# Grove_-_Alcohol_Sensor_v1_2.net
KiCad netlist of a schematic drawn in EAGLE
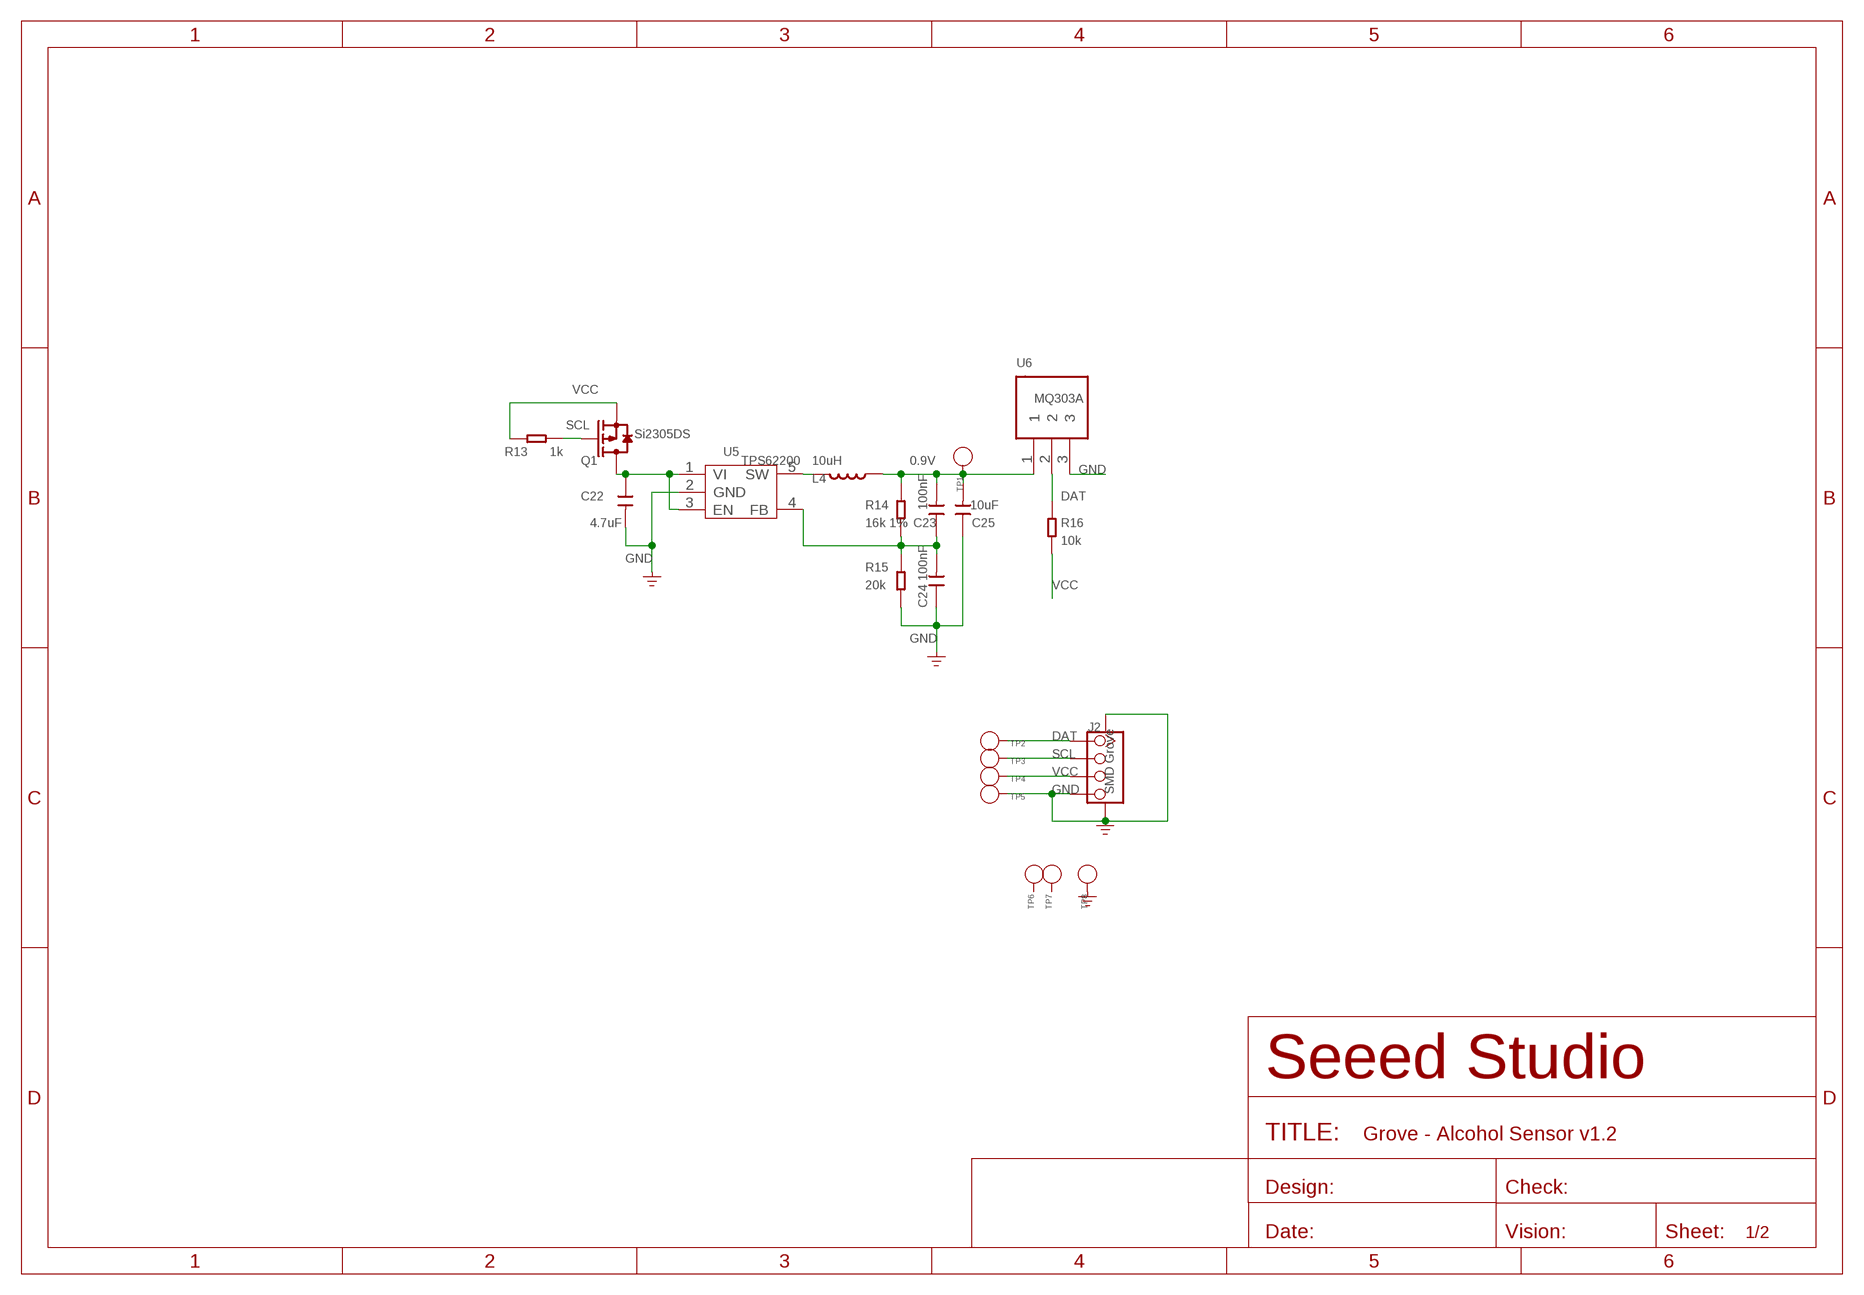
[diagram p0: schematic, sheet 1]
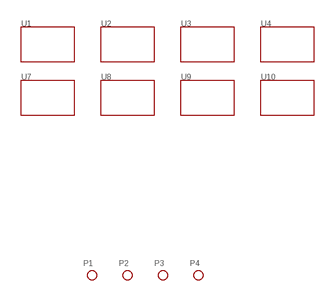
[diagram p1: schematic, sheet 2]

(export (version "E")
  (design (tool "Eeschema 10.0.6"))
  (components
    (comp (ref "P1")
      (value "PAD-MARK")
      (footprint "eagle-import:ROUND-MARK-1.0")
      (fields (field (name "PARTNO") "DNP"))
      (libsource (lib "eagle-import") (part "PAD-MARK"))
    )
    (comp (ref "P2")
      (value "PAD-MARK")
      (footprint "eagle-import:ROUND-MARK-1.0")
      (fields (field (name "PARTNO") "DNP"))
      (libsource (lib "eagle-import") (part "PAD-MARK"))
    )
    (comp (ref "P3")
      (value "PAD-MARK")
      (footprint "eagle-import:ROUND-MARK-1.0")
      (fields (field (name "PARTNO") "DNP"))
      (libsource (lib "eagle-import") (part "PAD-MARK"))
    )
    (comp (ref "P4")
      (value "PAD-MARK")
      (footprint "eagle-import:ROUND-MARK-1.0")
      (fields (field (name "PARTNO") "DNP"))
      (libsource (lib "eagle-import") (part "PAD-MARK"))
    )
    (comp (ref "U1")
      (value "TWIG'2U'")
      (footprint "eagle-import:GROVE-TEST-PLATFORM")
      (libsource (lib "eagle-import") (part "TWIG'2U'"))
    )
    (comp (ref "U2")
      (value "TWIG'2U'")
      (footprint "eagle-import:GROVE-TEST-PLATFORM")
      (libsource (lib "eagle-import") (part "TWIG'2U'"))
    )
    (comp (ref "U3")
      (value "TWIG'2U'")
      (footprint "eagle-import:GROVE-TEST-PLATFORM")
      (libsource (lib "eagle-import") (part "TWIG'2U'"))
    )
    (comp (ref "U4")
      (value "TWIG'2U'")
      (footprint "eagle-import:GROVE-TEST-PLATFORM")
      (libsource (lib "eagle-import") (part "TWIG'2U'"))
    )
    (comp (ref "U7")
      (value "TWIG'2U'")
      (footprint "eagle-import:GROVE-TEST-PLATFORM")
      (libsource (lib "eagle-import") (part "TWIG'2U'"))
    )
    (comp (ref "U8")
      (value "TWIG'2U'")
      (footprint "eagle-import:GROVE-TEST-PLATFORM")
      (libsource (lib "eagle-import") (part "TWIG'2U'"))
    )
    (comp (ref "U9")
      (value "TWIG'2U'")
      (footprint "eagle-import:GROVE-TEST-PLATFORM")
      (libsource (lib "eagle-import") (part "TWIG'2U'"))
    )
    (comp (ref "U10")
      (value "TWIG'2U'")
      (footprint "eagle-import:GROVE-TEST-PLATFORM")
      (libsource (lib "eagle-import") (part "TWIG'2U'"))
    )
    (comp (ref "C22")
      (value "4.7uF")
      (footprint "eagle-import:C0805")
      (libsource (lib "eagle-import") (part "C-0805"))
    )
    (comp (ref "C23")
      (value "100nF")
      (footprint "eagle-import:C0603")
      (libsource (lib "eagle-import") (part "C-0603"))
    )
    (comp (ref "C24")
      (value "100nF")
      (footprint "eagle-import:C0603")
      (libsource (lib "eagle-import") (part "C-0603"))
    )
    (comp (ref "C25")
      (value "10uF")
      (footprint "eagle-import:C0805")
      (libsource (lib "eagle-import") (part "C-0805"))
    )
    (comp (ref "J2")
      (value "SMD Grove")
      (footprint "eagle-import:4P-SMD-2.0")
      (libsource (lib "eagle-import") (part "TWIG-4P-2.0-SMD-FEMALE-REINFORCE'DD'"))
    )
    (comp (ref "L4")
      (value "10uH")
      (footprint "eagle-import:PIO73")
      (libsource (lib "eagle-import") (part "L'PIO73'"))
    )
    (comp (ref "Q1")
      (value "Si2305DS")
      (footprint "eagle-import:SOT23")
      (libsource (lib "eagle-import") (part "MOSFET-P'SI2323CDS/SI2305DS{lt}BR{gt}'"))
    )
    (comp (ref "R13")
      (value "1k")
      (footprint "eagle-import:R0603")
      (libsource (lib "eagle-import") (part "R-0603"))
    )
    (comp (ref "R14")
      (value "16k 1%")
      (footprint "eagle-import:R0603")
      (libsource (lib "eagle-import") (part "R-0603"))
    )
    (comp (ref "R15")
      (value "20k")
      (footprint "eagle-import:R0603")
      (libsource (lib "eagle-import") (part "R-0603"))
    )
    (comp (ref "R16")
      (value "10k")
      (footprint "eagle-import:R0603")
      (libsource (lib "eagle-import") (part "R-0603"))
    )
    (comp (ref "TP1")
      (value "PAD-TEST-POINT'4545'")
      (footprint "eagle-import:TP_4545")
      (fields (field (name "PARTNO") "DNP"))
      (libsource (lib "eagle-import") (part "PAD-TEST-POINT'4545'"))
    )
    (comp (ref "TP2")
      (value "PAD-TEST-POINT'4545'")
      (footprint "eagle-import:TP_4545")
      (fields (field (name "PARTNO") "DNP"))
      (libsource (lib "eagle-import") (part "PAD-TEST-POINT'4545'"))
    )
    (comp (ref "TP3")
      (value "PAD-TEST-POINT'4545'")
      (footprint "eagle-import:TP_4545")
      (fields (field (name "PARTNO") "DNP"))
      (libsource (lib "eagle-import") (part "PAD-TEST-POINT'4545'"))
    )
    (comp (ref "TP4")
      (value "PAD-TEST-POINT'4545'")
      (footprint "eagle-import:TP_4545")
      (fields (field (name "PARTNO") "DNP"))
      (libsource (lib "eagle-import") (part "PAD-TEST-POINT'4545'"))
    )
    (comp (ref "TP5")
      (value "PAD-TEST-POINT'4545'")
      (footprint "eagle-import:TP_4545")
      (fields (field (name "PARTNO") "DNP"))
      (libsource (lib "eagle-import") (part "PAD-TEST-POINT'4545'"))
    )
    (comp (ref "TP6")
      (value "PAD-TEST-POINT'4545'")
      (footprint "eagle-import:TP_4545")
      (fields (field (name "PARTNO") "DNP"))
      (libsource (lib "eagle-import") (part "PAD-TEST-POINT'4545'"))
    )
    (comp (ref "TP7")
      (value "PAD-TEST-POINT'4545'")
      (footprint "eagle-import:TP_4545")
      (fields (field (name "PARTNO") "DNP"))
      (libsource (lib "eagle-import") (part "PAD-TEST-POINT'4545'"))
    )
    (comp (ref "TP8")
      (value "PAD-TEST-POINT'4545'")
      (footprint "eagle-import:TP_4545")
      (fields (field (name "PARTNO") "DNP"))
      (libsource (lib "eagle-import") (part "PAD-TEST-POINT'4545'"))
    )
    (comp (ref "U5")
      (value "TPS62200")
      (footprint "eagle-import:SOT23-5")
      (libsource (lib "eagle-import") (part "TPS62200DBV"))
    )
    (comp (ref "U6")
      (value "MQ303A")
      (footprint "eagle-import:MQ303A")
      (libsource (lib "eagle-import") (part "MQ303A"))
    )
  )
  (nets
    (net (code "1") (name "0.9V") (class "Default")
      (node (ref "C23") (pin "2") (pinfunction "2_2") (pintype "passive"))
      (node (ref "C25") (pin "2") (pinfunction "2_2") (pintype "passive"))
      (node (ref "L4") (pin "2") (pinfunction "2_2") (pintype "passive"))
      (node (ref "R14") (pin "1") (pinfunction "1_1") (pintype "passive"))
      (node (ref "TP1") (pin "T") (pinfunction "T_T") (pintype "bidirectional"))
      (node (ref "U6") (pin "1") (pinfunction "1_1") (pintype "bidirectional"))
    )
    (net (code "2") (name "DAT") (class "Default")
      (node (ref "J2") (pin "1") (pinfunction "1_1") (pintype "bidirectional"))
      (node (ref "R16") (pin "1") (pinfunction "1_1") (pintype "passive"))
      (node (ref "TP2") (pin "T") (pinfunction "T_T") (pintype "bidirectional"))
      (node (ref "U6") (pin "2") (pinfunction "2_2") (pintype "bidirectional"))
    )
    (net (code "3") (name "GND") (class "Default")
      (node (ref "C22") (pin "2") (pinfunction "2_2") (pintype "passive"))
      (node (ref "C24") (pin "1") (pinfunction "1_1") (pintype "passive"))
      (node (ref "C25") (pin "1") (pinfunction "1_1") (pintype "passive"))
      (node (ref "J2") (pin "4") (pinfunction "4_4") (pintype "bidirectional"))
      (node (ref "J2") (pin "SS1") (pinfunction "SS1_SS1") (pintype "bidirectional"))
      (node (ref "J2") (pin "SS2") (pinfunction "SS2_SS2") (pintype "bidirectional"))
      (node (ref "R15") (pin "2") (pinfunction "2_2") (pintype "passive"))
      (node (ref "TP5") (pin "T") (pinfunction "T_T") (pintype "bidirectional"))
      (node (ref "TP8") (pin "T") (pinfunction "T_T") (pintype "bidirectional"))
      (node (ref "U5") (pin "2") (pinfunction "GND_2") (pintype "power_in"))
      (node (ref "U6") (pin "3") (pinfunction "3_3") (pintype "bidirectional"))
    )
    (net (code "4") (name "Net-(Q1-D)") (class "Default")
      (node (ref "C22") (pin "1") (pinfunction "1_1") (pintype "passive"))
      (node (ref "Q1") (pin "3") (pinfunction "D_3") (pintype "passive"))
      (node (ref "U5") (pin "1") (pinfunction "VI_1") (pintype "input"))
      (node (ref "U5") (pin "3") (pinfunction "EN_3") (pintype "input"))
    )
    (net (code "5") (name "Net-(U5-FB)") (class "Default")
      (node (ref "C23") (pin "1") (pinfunction "1_1") (pintype "passive"))
      (node (ref "C24") (pin "2") (pinfunction "2_2") (pintype "passive"))
      (node (ref "R14") (pin "2") (pinfunction "2_2") (pintype "passive"))
      (node (ref "R15") (pin "1") (pinfunction "1_1") (pintype "passive"))
      (node (ref "U5") (pin "4") (pinfunction "FB_4") (pintype "input"))
    )
    (net (code "6") (name "Net-(U5-SW)") (class "Default")
      (node (ref "L4") (pin "1") (pinfunction "1_1") (pintype "passive"))
      (node (ref "U5") (pin "5") (pinfunction "SW_5") (pintype "bidirectional"))
    )
    (net (code "7") (name "SCL") (class "Default")
      (node (ref "J2") (pin "2") (pinfunction "2_2") (pintype "bidirectional"))
      (node (ref "Q1") (pin "1") (pinfunction "G_1") (pintype "passive"))
      (node (ref "R13") (pin "1") (pinfunction "1_1") (pintype "passive"))
      (node (ref "TP3") (pin "T") (pinfunction "T_T") (pintype "bidirectional"))
    )
    (net (code "8") (name "VCC") (class "Default")
      (node (ref "J2") (pin "3") (pinfunction "3_3") (pintype "bidirectional"))
      (node (ref "Q1") (pin "2") (pinfunction "S_2") (pintype "passive"))
      (node (ref "R13") (pin "2") (pinfunction "2_2") (pintype "passive"))
      (node (ref "R16") (pin "2") (pinfunction "2_2") (pintype "passive"))
      (node (ref "TP4") (pin "T") (pinfunction "T_T") (pintype "bidirectional"))
    )
    (net (code "9") (name "unconnected-(TP6-PadT)") (class "Default")
      (node (ref "TP6") (pin "T") (pinfunction "T_T") (pintype "bidirectional"))
    )
    (net (code "10") (name "unconnected-(TP7-PadT)") (class "Default")
      (node (ref "TP7") (pin "T") (pinfunction "T_T") (pintype "bidirectional"))
    )
  )
)
